# Adapter_UNIT_SPI_TO_INTAN.net
KiCad netlist of a schematic drawn in Altium Designer
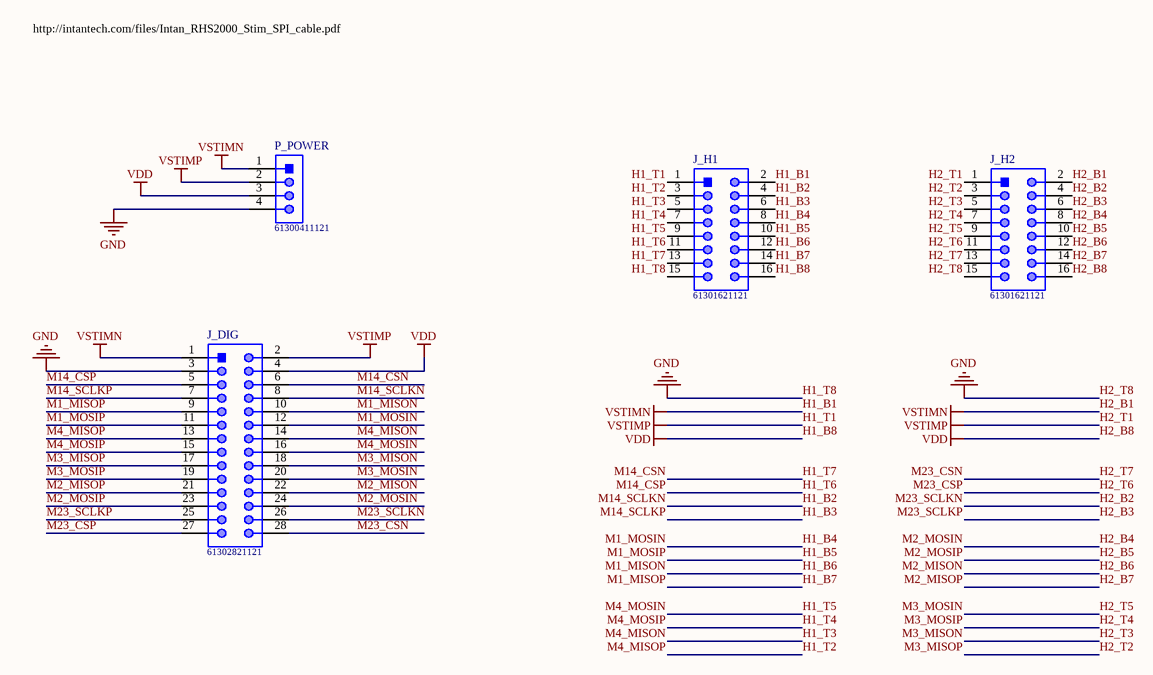
[diagram p0: Adapter_UNIT_SPI_TO_INTAN.SchDoc]

(export (version "E")
  (design (tool "Eeschema 10.0.6"))
  (components
    (comp (ref "J_DIG")
      (value "61302821121")
      (footprint "61302821121")
      (description "THT Vertical Pin Header WR-PHD, Pitch 2.54 mm, Dual Row, 28 pins")
      (fields (field (name "MANUFACTURER") "Wurth Elektronik") (field (name "PUBLISHER") "WurthElektronik"))
      (libsource (lib "Altium Content Vault") (part "WE-CN-2P-M-R28"))
    )
    (comp (ref "J_H1")
      (value "61301621121")
      (footprint "61301621121")
      (description "THT Vertical Pin Header WR-PHD, Pitch 2.54 mm, Dual Row, 16 pins")
      (fields (field (name "MANUFACTURER") "Wurth Elektronik") (field (name "PUBLISHER") "WurthElektronik"))
      (libsource (lib "Altium Content Vault") (part "WE-CN-2P-M-R16"))
    )
    (comp (ref "J_H2")
      (value "61301621121")
      (footprint "61301621121")
      (description "THT Vertical Pin Header WR-PHD, Pitch 2.54 mm, Dual Row, 16 pins")
      (fields (field (name "MANUFACTURER") "Wurth Elektronik") (field (name "PUBLISHER") "WurthElektronik"))
      (libsource (lib "Altium Content Vault") (part "WE-CN-2P-M-R16"))
    )
    (comp (ref "P_POWER")
      (value "61300411121")
      (footprint "61300411121")
      (description "THT Vertical Pin Header WR-PHD, Pitch 2.54 mm, Single Row, 4 pins")
      (fields (field (name "MANUFACTURER") "Wurth Elektronik") (field (name "PUBLISHER") "WurthElektronik"))
      (libsource (lib "Altium Content Vault") (part "WE-CN-1P-M-R4"))
    )
  )
  (nets
    (net (code "1") (name "/H1_B2") (class "Default")
      (node (ref "J_DIG") (pin "8") (pinfunction "8_8") (pintype "passive"))
      (node (ref "J_H1") (pin "4") (pinfunction "4_4") (pintype "passive"))
    )
    (net (code "2") (name "/H1_B3") (class "Default")
      (node (ref "J_DIG") (pin "7") (pinfunction "7_7") (pintype "passive"))
      (node (ref "J_H1") (pin "6") (pinfunction "6_6") (pintype "passive"))
    )
    (net (code "3") (name "/H1_B4") (class "Default")
      (node (ref "J_DIG") (pin "12") (pinfunction "12_12") (pintype "passive"))
      (node (ref "J_H1") (pin "8") (pinfunction "8_8") (pintype "passive"))
    )
    (net (code "4") (name "/H1_B5") (class "Default")
      (node (ref "J_DIG") (pin "11") (pinfunction "11_11") (pintype "passive"))
      (node (ref "J_H1") (pin "10") (pinfunction "10_10") (pintype "passive"))
    )
    (net (code "5") (name "/H1_B6") (class "Default")
      (node (ref "J_DIG") (pin "10") (pinfunction "10_10") (pintype "passive"))
      (node (ref "J_H1") (pin "12") (pinfunction "12_12") (pintype "passive"))
    )
    (net (code "6") (name "/H1_B7") (class "Default")
      (node (ref "J_DIG") (pin "9") (pinfunction "9_9") (pintype "passive"))
      (node (ref "J_H1") (pin "14") (pinfunction "14_14") (pintype "passive"))
    )
    (net (code "7") (name "/H1_T2") (class "Default")
      (node (ref "J_DIG") (pin "13") (pinfunction "13_13") (pintype "passive"))
      (node (ref "J_H1") (pin "3") (pinfunction "3_3") (pintype "passive"))
    )
    (net (code "8") (name "/H1_T3") (class "Default")
      (node (ref "J_DIG") (pin "14") (pinfunction "14_14") (pintype "passive"))
      (node (ref "J_H1") (pin "5") (pinfunction "5_5") (pintype "passive"))
    )
    (net (code "9") (name "/H1_T4") (class "Default")
      (node (ref "J_DIG") (pin "15") (pinfunction "15_15") (pintype "passive"))
      (node (ref "J_H1") (pin "7") (pinfunction "7_7") (pintype "passive"))
    )
    (net (code "10") (name "/H1_T5") (class "Default")
      (node (ref "J_DIG") (pin "16") (pinfunction "16_16") (pintype "passive"))
      (node (ref "J_H1") (pin "9") (pinfunction "9_9") (pintype "passive"))
    )
    (net (code "11") (name "/H1_T6") (class "Default")
      (node (ref "J_DIG") (pin "5") (pinfunction "5_5") (pintype "passive"))
      (node (ref "J_H1") (pin "11") (pinfunction "11_11") (pintype "passive"))
    )
    (net (code "12") (name "/H1_T7") (class "Default")
      (node (ref "J_DIG") (pin "6") (pinfunction "6_6") (pintype "passive"))
      (node (ref "J_H1") (pin "13") (pinfunction "13_13") (pintype "passive"))
    )
    (net (code "13") (name "/H2_B2") (class "Default")
      (node (ref "J_DIG") (pin "26") (pinfunction "26_26") (pintype "passive"))
      (node (ref "J_H2") (pin "4") (pinfunction "4_4") (pintype "passive"))
    )
    (net (code "14") (name "/H2_B3") (class "Default")
      (node (ref "J_DIG") (pin "25") (pinfunction "25_25") (pintype "passive"))
      (node (ref "J_H2") (pin "6") (pinfunction "6_6") (pintype "passive"))
    )
    (net (code "15") (name "/H2_B4") (class "Default")
      (node (ref "J_DIG") (pin "24") (pinfunction "24_24") (pintype "passive"))
      (node (ref "J_H2") (pin "8") (pinfunction "8_8") (pintype "passive"))
    )
    (net (code "16") (name "/H2_B5") (class "Default")
      (node (ref "J_DIG") (pin "23") (pinfunction "23_23") (pintype "passive"))
      (node (ref "J_H2") (pin "10") (pinfunction "10_10") (pintype "passive"))
    )
    (net (code "17") (name "/H2_B6") (class "Default")
      (node (ref "J_DIG") (pin "22") (pinfunction "22_22") (pintype "passive"))
      (node (ref "J_H2") (pin "12") (pinfunction "12_12") (pintype "passive"))
    )
    (net (code "18") (name "/H2_B7") (class "Default")
      (node (ref "J_DIG") (pin "21") (pinfunction "21_21") (pintype "passive"))
      (node (ref "J_H2") (pin "14") (pinfunction "14_14") (pintype "passive"))
    )
    (net (code "19") (name "/H2_T2") (class "Default")
      (node (ref "J_DIG") (pin "17") (pinfunction "17_17") (pintype "passive"))
      (node (ref "J_H2") (pin "3") (pinfunction "3_3") (pintype "passive"))
    )
    (net (code "20") (name "/H2_T3") (class "Default")
      (node (ref "J_DIG") (pin "18") (pinfunction "18_18") (pintype "passive"))
      (node (ref "J_H2") (pin "5") (pinfunction "5_5") (pintype "passive"))
    )
    (net (code "21") (name "/H2_T4") (class "Default")
      (node (ref "J_DIG") (pin "19") (pinfunction "19_19") (pintype "passive"))
      (node (ref "J_H2") (pin "7") (pinfunction "7_7") (pintype "passive"))
    )
    (net (code "22") (name "/H2_T5") (class "Default")
      (node (ref "J_DIG") (pin "20") (pinfunction "20_20") (pintype "passive"))
      (node (ref "J_H2") (pin "9") (pinfunction "9_9") (pintype "passive"))
    )
    (net (code "23") (name "/H2_T6") (class "Default")
      (node (ref "J_DIG") (pin "27") (pinfunction "27_27") (pintype "passive"))
      (node (ref "J_H2") (pin "11") (pinfunction "11_11") (pintype "passive"))
    )
    (net (code "24") (name "/H2_T7") (class "Default")
      (node (ref "J_DIG") (pin "28") (pinfunction "28_28") (pintype "passive"))
      (node (ref "J_H2") (pin "13") (pinfunction "13_13") (pintype "passive"))
    )
    (net (code "25") (name "GND") (class "Default")
      (node (ref "J_DIG") (pin "3") (pinfunction "3_3") (pintype "passive"))
      (node (ref "J_H1") (pin "15") (pinfunction "15_15") (pintype "passive"))
      (node (ref "J_H2") (pin "15") (pinfunction "15_15") (pintype "passive"))
      (node (ref "P_POWER") (pin "4") (pinfunction "4_4") (pintype "passive"))
    )
    (net (code "26") (name "VDD") (class "Default")
      (node (ref "J_DIG") (pin "4") (pinfunction "4_4") (pintype "passive"))
      (node (ref "J_H1") (pin "16") (pinfunction "16_16") (pintype "passive"))
      (node (ref "J_H2") (pin "16") (pinfunction "16_16") (pintype "passive"))
      (node (ref "P_POWER") (pin "3") (pinfunction "3_3") (pintype "passive"))
    )
    (net (code "27") (name "VSTIMN") (class "Default")
      (node (ref "J_DIG") (pin "1") (pinfunction "1_1") (pintype "passive"))
      (node (ref "J_H1") (pin "2") (pinfunction "2_2") (pintype "passive"))
      (node (ref "J_H2") (pin "2") (pinfunction "2_2") (pintype "passive"))
      (node (ref "P_POWER") (pin "1") (pinfunction "1_1") (pintype "passive"))
    )
    (net (code "28") (name "VSTIMP") (class "Default")
      (node (ref "J_DIG") (pin "2") (pinfunction "2_2") (pintype "passive"))
      (node (ref "J_H1") (pin "1") (pinfunction "1_1") (pintype "passive"))
      (node (ref "J_H2") (pin "1") (pinfunction "1_1") (pintype "passive"))
      (node (ref "P_POWER") (pin "2") (pinfunction "2_2") (pintype "passive"))
    )
  )
)
